# SCH_New-Project_2024-10-10.net
KiCad netlist of a schematic drawn in EasyEDA
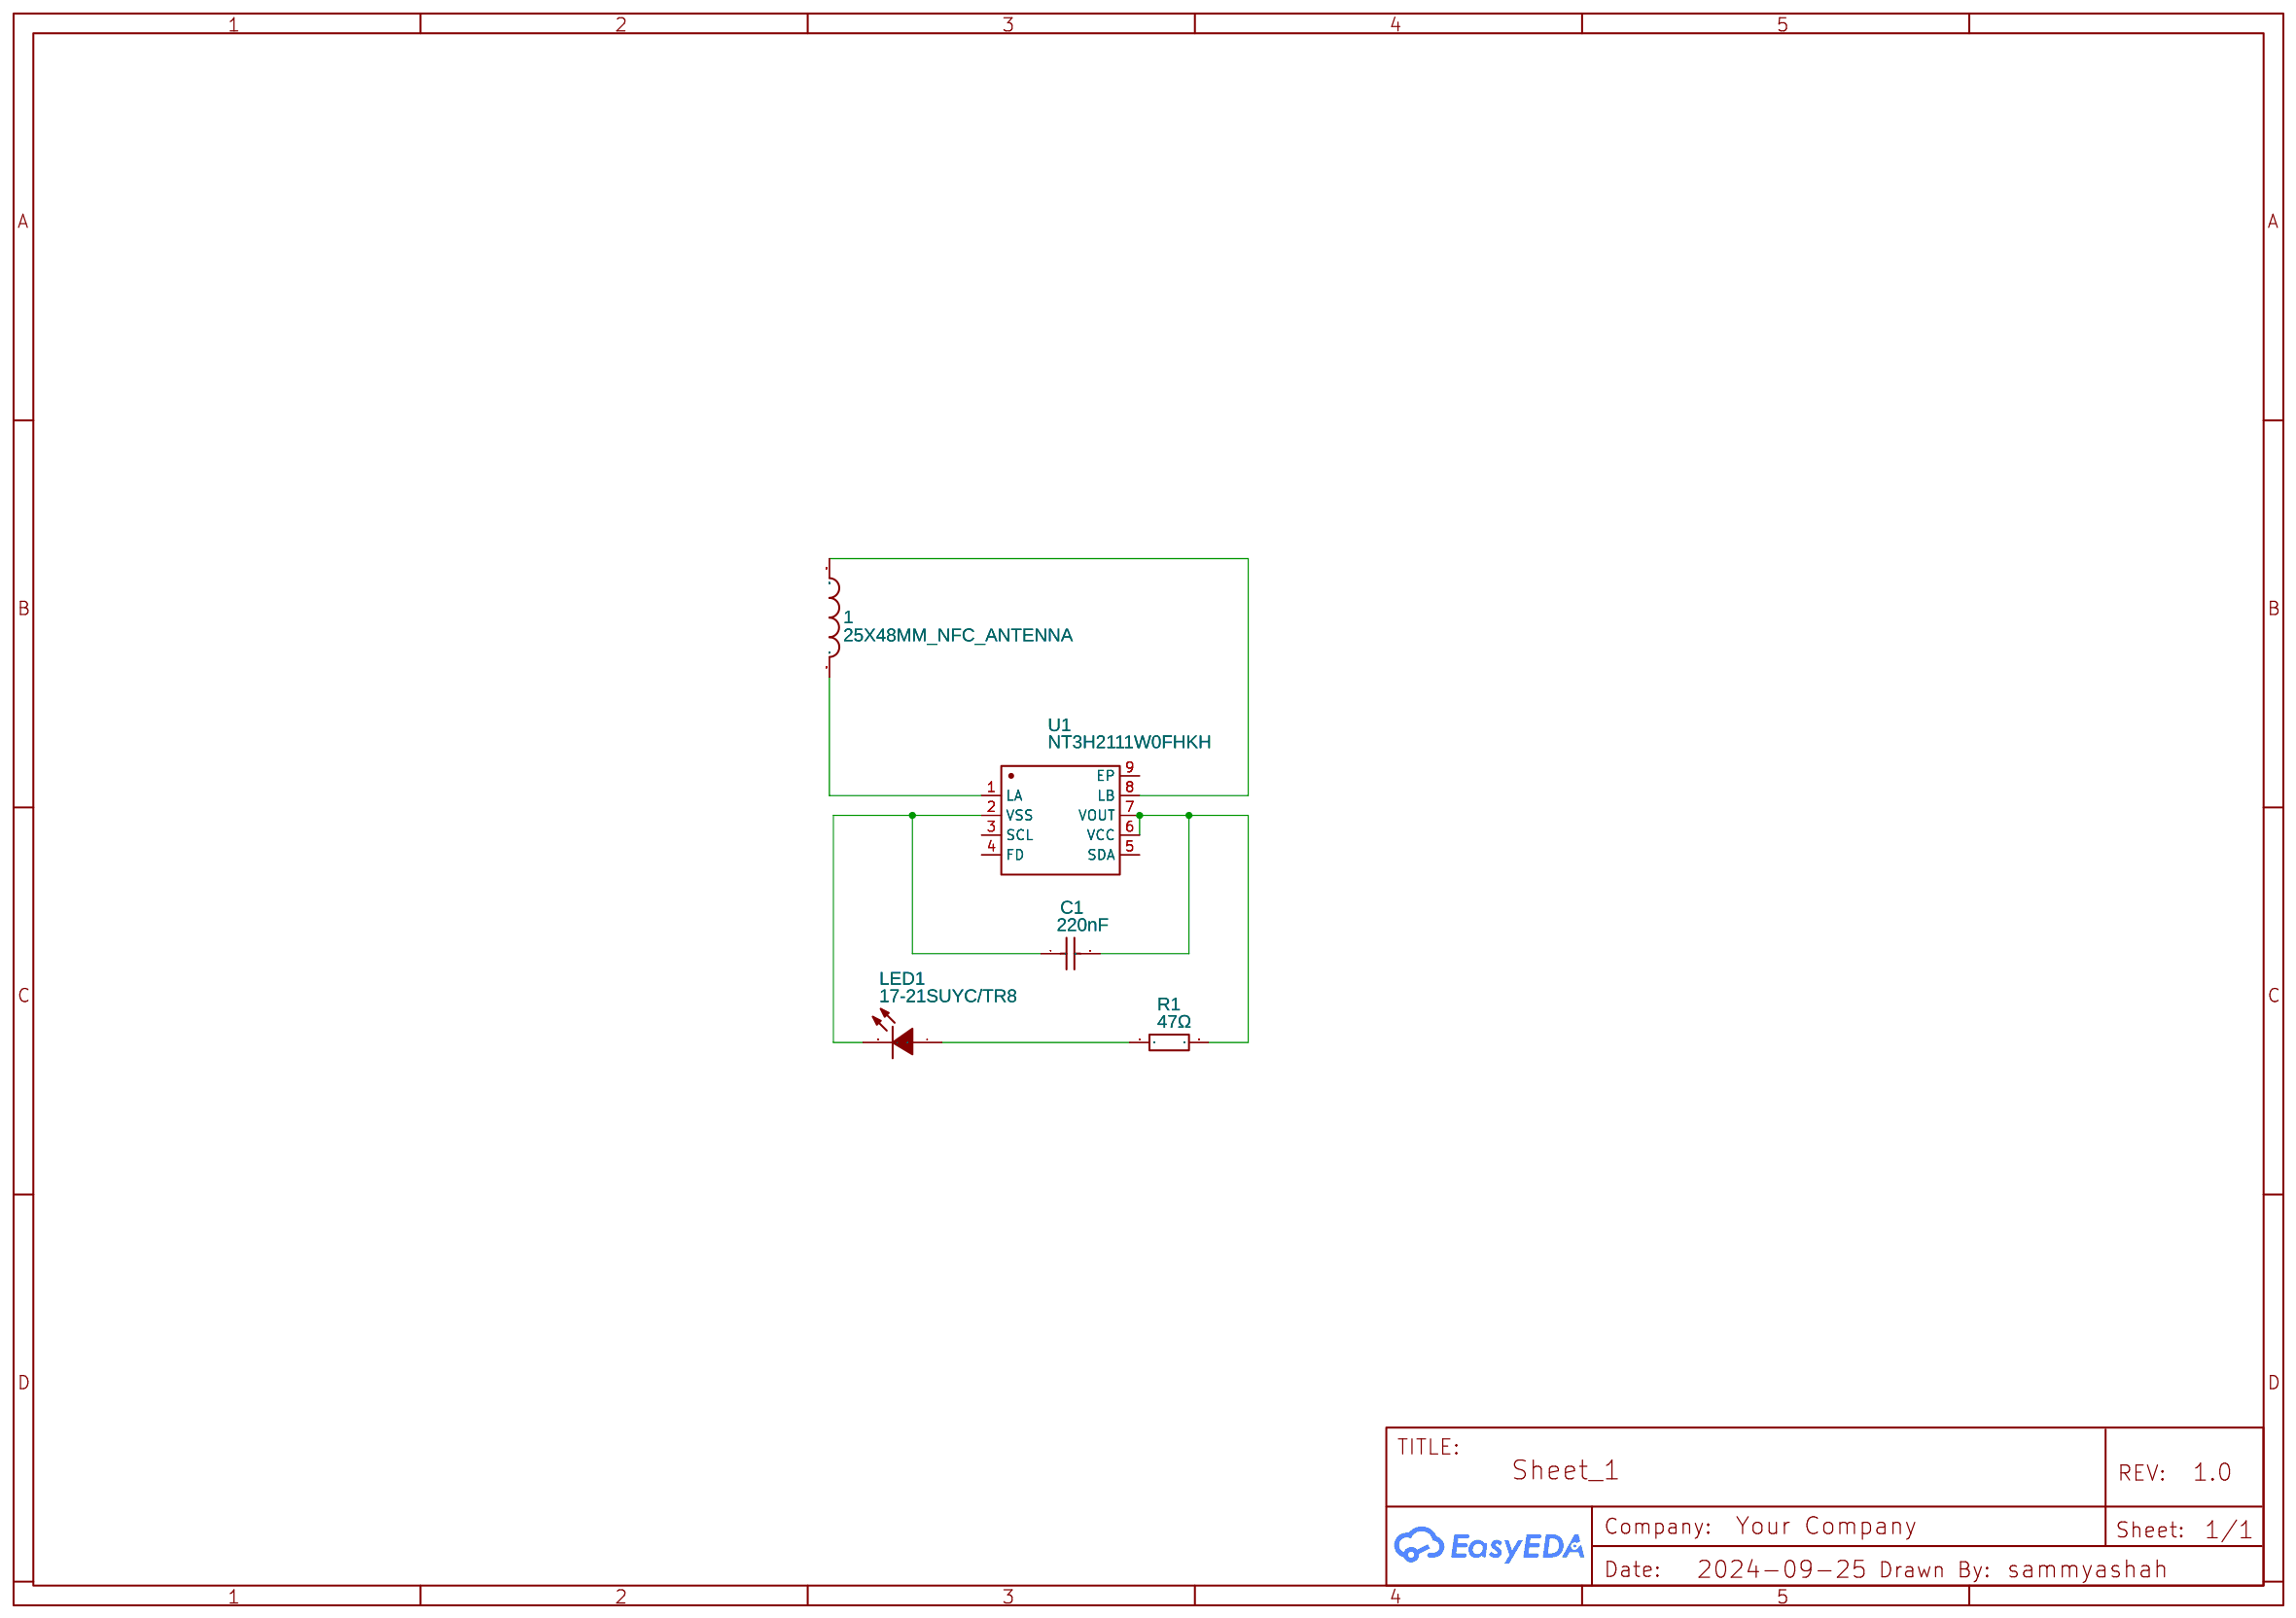
[diagram p0: schematic sheet]

(export (version "E")
  (design (tool "Eeschema 10.0.6"))
  (components
    (comp (ref "1") (value "25X48MM_NFC_ANTENNA") (libsource (lib "") (part "25X48MM_NFC_ANTENNA")))
    (comp (ref "C1")
      (value "220nF")
      (fields
        (field (name "Manufacturer Part") "CL10B224KA8NNNC")
        (field (name "Manufacturer") "SAMSUNG(三星)")
      )
      (libsource (lib "") (part "CL10B224KA8NNNC"))
    )
    (comp (ref "LED1")
      (value "17-21SUYC/TR8")
      (fields (field (name "Manufacturer Part") "KT-0805黄灯") (field (name "Manufacturer") "KENTO"))
      (libsource (lib "") (part "17-21SUYC/TR8"))
    )
    (comp (ref "R1")
      (value "47Ω")
      (fields
        (field (name "Manufacturer Part") "0603WAF470JT5E")
        (field (name "Manufacturer") "UNI-ROYAL(厚声)")
      )
      (libsource (lib "") (part "0603WAF470JT5E"))
    )
    (comp (ref "U1")
      (value "NT3H2111W0FHKH")
      (fields (field (name "Manufacturer") "NXP(恩智浦)"))
      (libsource (lib "") (part "NT3H2111W0FHKH"))
    )
  )
  (nets
    (net (code "1") (name "Net-(LED1-+)") (class "Default")
      (node (ref "LED1") (pin "1") (pinfunction "+_1") (pintype "unspecified"))
      (node (ref "R1") (pin "1") (pinfunction "1_1") (pintype "input"))
    )
    (net (code "2") (name "Net-(LED1--)") (class "Default")
      (node (ref "C1") (pin "1") (pinfunction "1_1") (pintype "input"))
      (node (ref "LED1") (pin "2") (pinfunction "-_2") (pintype "unspecified"))
      (node (ref "U1") (pin "2") (pinfunction "VSS_2") (pintype "unspecified"))
    )
    (net (code "3") (name "Net-(U1-LA)") (class "Default")
      (node (ref "1") (pin "P$2") (pinfunction "P$2_P$2") (pintype "bidirectional"))
      (node (ref "U1") (pin "1") (pinfunction "LA_1") (pintype "unspecified"))
    )
    (net (code "4") (name "Net-(U1-LB)") (class "Default")
      (node (ref "1") (pin "P$1") (pinfunction "P$1_P$1") (pintype "bidirectional"))
      (node (ref "U1") (pin "8") (pinfunction "LB_8") (pintype "unspecified"))
    )
    (net (code "5") (name "Net-(U1-VCC)") (class "Default")
      (node (ref "C1") (pin "2") (pinfunction "2_2") (pintype "input"))
      (node (ref "R1") (pin "2") (pinfunction "2_2") (pintype "input"))
      (node (ref "U1") (pin "6") (pinfunction "VCC_6") (pintype "unspecified"))
      (node (ref "U1") (pin "7") (pinfunction "VOUT_7") (pintype "unspecified"))
    )
    (net (code "6") (name "unconnected-(U1-EP-Pad9)") (class "Default")
      (node (ref "U1") (pin "9") (pinfunction "EP_9") (pintype "unspecified"))
    )
    (net (code "7") (name "unconnected-(U1-FD-Pad4)") (class "Default")
      (node (ref "U1") (pin "4") (pinfunction "FD_4") (pintype "unspecified"))
    )
    (net (code "8") (name "unconnected-(U1-SCL-Pad3)") (class "Default")
      (node (ref "U1") (pin "3") (pinfunction "SCL_3") (pintype "unspecified"))
    )
    (net (code "9") (name "unconnected-(U1-SDA-Pad5)") (class "Default")
      (node (ref "U1") (pin "5") (pinfunction "SDA_5") (pintype "unspecified"))
    )
  )
)
